# magic.net
KiCad netlist of a schematic drawn in EAGLE
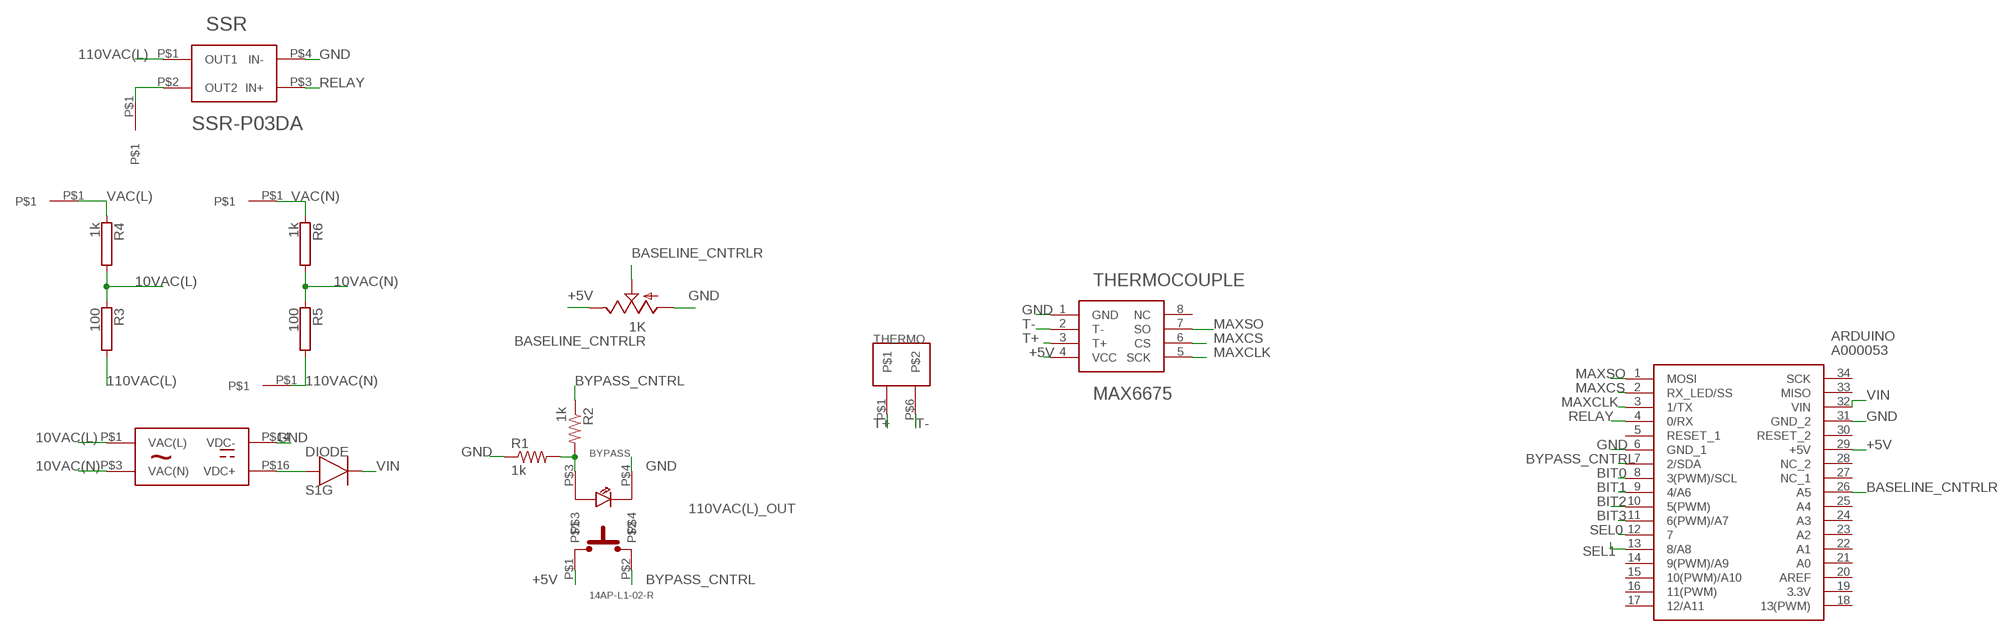
[diagram p0: schematic, sheet 1]
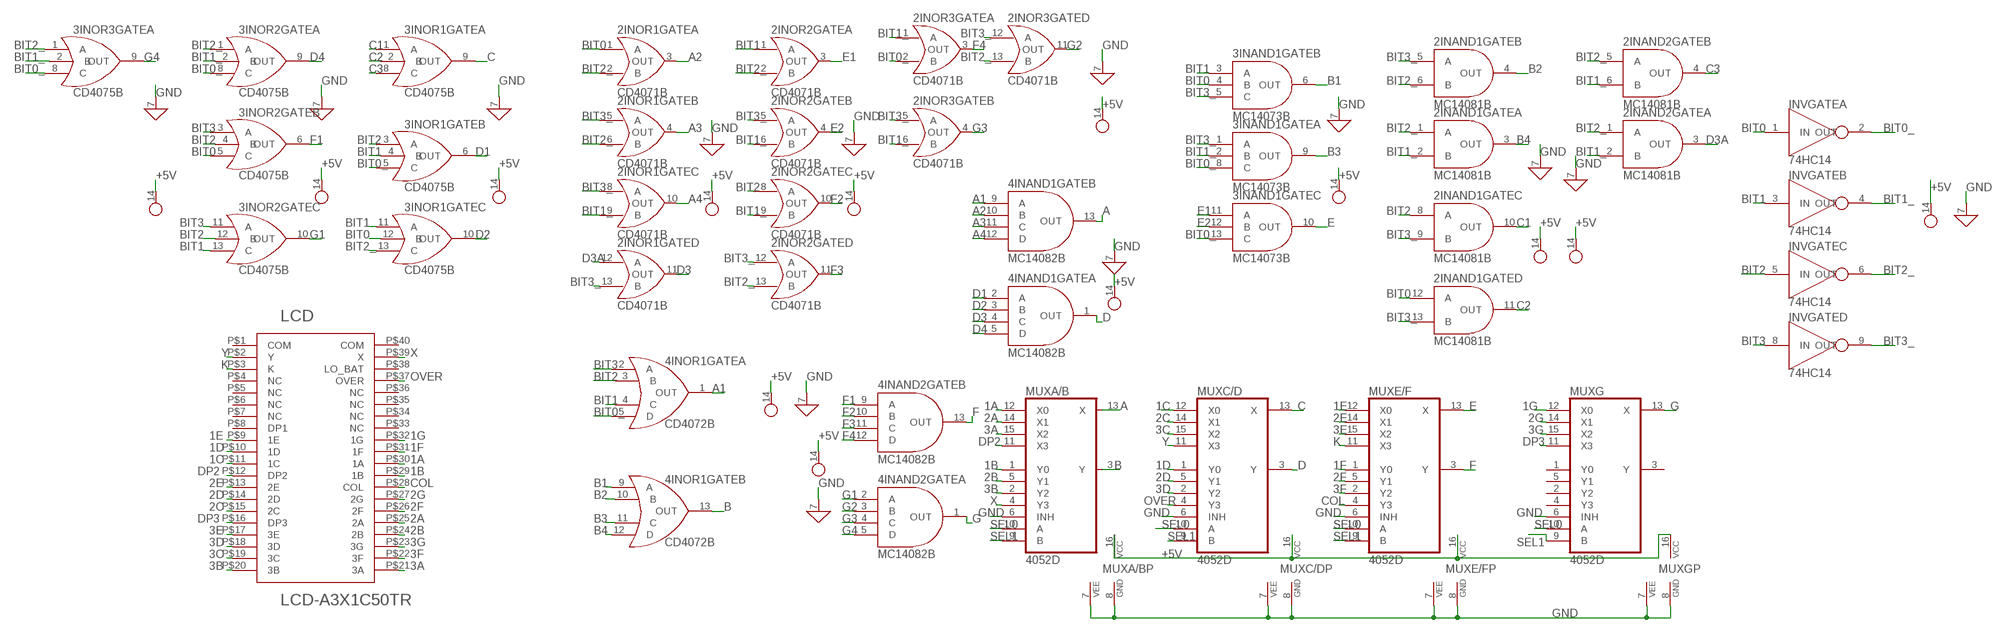
[diagram p1: schematic, sheet 2]

(export (version "E")
  (design (tool "Eeschema 10.0.6"))
  (components
    (comp (ref "110VAC(L)_OUT")
      (value "6-GAUGE")
      (footprint "eagle-import:6-GAUGE")
      (libsource (lib "eagle-import") (part "6-GAUGE"))
    )
    (comp (ref "110VAC(N)_OUT")
      (value "6-GAUGE")
      (footprint "eagle-import:6-GAUGE")
      (libsource (lib "eagle-import") (part "6-GAUGE"))
    )
    (comp (ref "AC(L)_IN")
      (value "6-GAUGE")
      (footprint "eagle-import:6-GAUGE")
      (libsource (lib "eagle-import") (part "6-GAUGE"))
    )
    (comp (ref "AC(N)_IN")
      (value "6-GAUGE")
      (footprint "eagle-import:6-GAUGE")
      (libsource (lib "eagle-import") (part "6-GAUGE"))
    )
    (comp (ref "ARDUINO")
      (value "A000053")
      (footprint "eagle-import:HDRV34W70P1570X254_2X17_4900X1")
      (fields (field (name "MOUSER_PART_NUMBER") "782-A000053") (field (name "RS_PART_NUMBER") "7717667"))
      (libsource (lib "eagle-import") (part "A000053"))
    )
    (comp (ref "BASELINE_CNTRLR")
      (value "1K")
      (footprint "eagle-import:PT-10")
      (libsource (lib "eagle-import") (part "TRIM_US-PT10"))
    )
    (comp (ref "BYPASS")
      (value "14AP-L1-02-R")
      (footprint "eagle-import:14XX-LX-0X-X")
      (libsource (lib "eagle-import") (part "14AP-L1-02-R"))
    )
    (comp (ref "DIODE")
      (value "S1G")
      (footprint "eagle-import:S1G")
      (libsource (lib "eagle-import") (part "S1G"))
    )
    (comp (ref "R1")
      (value "1k")
      (footprint "eagle-import:M1206")
      (libsource (lib "eagle-import") (part "R-US_M1206"))
    )
    (comp (ref "R2")
      (value "1k")
      (footprint "eagle-import:M1206")
      (libsource (lib "eagle-import") (part "R-US_M1206"))
    )
    (comp (ref "R3")
      (value "100")
      (footprint "eagle-import:TO-247-2V")
      (libsource (lib "eagle-import") (part "RMG100-V"))
    )
    (comp (ref "R4")
      (value "1k")
      (footprint "eagle-import:TO-247-2V")
      (libsource (lib "eagle-import") (part "RMG100-V"))
    )
    (comp (ref "R5")
      (value "100")
      (footprint "eagle-import:TO-247-2V")
      (libsource (lib "eagle-import") (part "RMG100-V"))
    )
    (comp (ref "R6")
      (value "1k")
      (footprint "eagle-import:TO-247-2V")
      (libsource (lib "eagle-import") (part "RMG100-V"))
    )
    (comp (ref "SSR")
      (value "SSR-P03DA")
      (footprint "eagle-import:SSR-P03DA")
      (libsource (lib "eagle-import") (part "SSR-P03DA"))
    )
    (comp (ref "THERMO")
      (value "PC6-16/2-G1-10,16")
      (footprint "eagle-import:PC6-16_2-G1-10,16")
      (libsource (lib "eagle-import") (part "PC6-16/2-G1-10,16"))
    )
    (comp (ref "THERMOCOUPLE")
      (value "MAX6675")
      (footprint "eagle-import:MAX6675")
      (libsource (lib "eagle-import") (part "MAX6675"))
    )
    (comp (ref "TRANSFORMER")
      (value "RAC04-09SC")
      (footprint "eagle-import:RAC04-09SC")
      (libsource (lib "eagle-import") (part "RAC04-09SC"))
    )
    (comp (ref "2INAND1")
      (value "MC14081B")
      (footprint "eagle-import:MC140XXBG")
      (libsource (lib "eagle-import") (part "MC14081B"))
    )
    (comp (ref "2INAND2")
      (value "MC14081B")
      (footprint "eagle-import:MC140XXBG")
      (libsource (lib "eagle-import") (part "MC14081B"))
    )
    (comp (ref "2INOR1")
      (value "CD4071B")
      (footprint "eagle-import:CD407XB")
      (libsource (lib "eagle-import") (part "CD4071B"))
    )
    (comp (ref "2INOR2")
      (value "CD4071B")
      (footprint "eagle-import:CD407XB")
      (libsource (lib "eagle-import") (part "CD4071B"))
    )
    (comp (ref "2INOR3")
      (value "CD4071B")
      (footprint "eagle-import:CD407XB")
      (libsource (lib "eagle-import") (part "CD4071B"))
    )
    (comp (ref "3INAND1")
      (value "MC14073B")
      (footprint "eagle-import:MC140XXBG")
      (libsource (lib "eagle-import") (part "MC14073B"))
    )
    (comp (ref "3INOR1")
      (value "CD4075B")
      (footprint "eagle-import:CD407XB")
      (libsource (lib "eagle-import") (part "CD4075B"))
    )
    (comp (ref "3INOR2")
      (value "CD4075B")
      (footprint "eagle-import:CD407XB")
      (libsource (lib "eagle-import") (part "CD4075B"))
    )
    (comp (ref "3INOR3")
      (value "CD4075B")
      (footprint "eagle-import:CD407XB")
      (libsource (lib "eagle-import") (part "CD4075B"))
    )
    (comp (ref "4INAND1")
      (value "MC14082B")
      (footprint "eagle-import:MC140XXBG")
      (libsource (lib "eagle-import") (part "MC14082B"))
    )
    (comp (ref "4INAND2")
      (value "MC14082B")
      (footprint "eagle-import:MC140XXBG")
      (libsource (lib "eagle-import") (part "MC14082B"))
    )
    (comp (ref "4INOR1")
      (value "CD4072B")
      (footprint "eagle-import:CD407XB")
      (libsource (lib "eagle-import") (part "CD4072B"))
    )
    (comp (ref "INV")
      (value "74HC14")
      (footprint "eagle-import:74HC14")
      (libsource (lib "eagle-import") (part "74HC14"))
    )
    (comp (ref "LCD")
      (value "LCD-A3X1C50TR")
      (footprint "eagle-import:LCD-A3X1C50TR")
      (libsource (lib "eagle-import") (part "LCD-A3X1C50TR"))
    )
    (comp (ref "MUXA/B")
      (value "4052D")
      (footprint "eagle-import:SO16")
      (libsource (lib "eagle-import") (part "4052D"))
    )
    (comp (ref "MUXC/D")
      (value "4052D")
      (footprint "eagle-import:SO16")
      (libsource (lib "eagle-import") (part "4052D"))
    )
    (comp (ref "MUXE/F")
      (value "4052D")
      (footprint "eagle-import:SO16")
      (libsource (lib "eagle-import") (part "4052D"))
    )
    (comp (ref "MUXG")
      (value "4052D")
      (footprint "eagle-import:SO16")
      (libsource (lib "eagle-import") (part "4052D"))
    )
  )
  (nets
    (net (code "1") (name "+5V") (class "Default")
      (node (ref "2INAND1") (pin "14") (pinfunction "1_14") (pintype "bidirectional"))
      (node (ref "2INAND2") (pin "14") (pinfunction "1_14") (pintype "bidirectional"))
      (node (ref "2INOR1") (pin "14") (pinfunction "1_14") (pintype "bidirectional"))
      (node (ref "2INOR2") (pin "14") (pinfunction "1_14") (pintype "bidirectional"))
      (node (ref "2INOR3") (pin "14") (pinfunction "1_14") (pintype "bidirectional"))
      (node (ref "3INAND1") (pin "14") (pinfunction "1_14") (pintype "bidirectional"))
      (node (ref "3INOR1") (pin "14") (pinfunction "1_14") (pintype "bidirectional"))
      (node (ref "3INOR2") (pin "14") (pinfunction "1_14") (pintype "bidirectional"))
      (node (ref "3INOR3") (pin "14") (pinfunction "1_14") (pintype "bidirectional"))
      (node (ref "4INAND1") (pin "14") (pinfunction "1_14") (pintype "bidirectional"))
      (node (ref "4INAND2") (pin "14") (pinfunction "1_14") (pintype "bidirectional"))
      (node (ref "4INOR1") (pin "14") (pinfunction "1_14") (pintype "bidirectional"))
      (node (ref "ARDUINO") (pin "29") (pinfunction "+5V_29") (pintype "bidirectional"))
      (node (ref "BASELINE_CNTRLR") (pin "E") (pinfunction "E_E") (pintype "passive"))
      (node (ref "BYPASS") (pin "P$1") (pinfunction "P$1_P$1") (pintype "bidirectional"))
      (node (ref "INV") (pin "14") (pinfunction "1_14") (pintype "bidirectional"))
      (node (ref "MUXA/B") (pin "16") (pinfunction "VCC_16") (pintype "power_in"))
      (node (ref "MUXC/D") (pin "16") (pinfunction "VCC_16") (pintype "power_in"))
      (node (ref "MUXE/F") (pin "16") (pinfunction "VCC_16") (pintype "power_in"))
      (node (ref "MUXG") (pin "16") (pinfunction "VCC_16") (pintype "power_in"))
      (node (ref "THERMOCOUPLE") (pin "4") (pinfunction "VCC_4") (pintype "bidirectional"))
    )
    (net (code "2") (name "1A") (class "Default")
      (node (ref "LCD") (pin "P$30") (pinfunction "1A_P$30") (pintype "bidirectional"))
      (node (ref "MUXA/B") (pin "12") (pinfunction "X0_12") (pintype "bidirectional"))
    )
    (net (code "3") (name "1B") (class "Default")
      (node (ref "LCD") (pin "P$29") (pinfunction "1B_P$29") (pintype "bidirectional"))
      (node (ref "MUXA/B") (pin "1") (pinfunction "Y0_1") (pintype "bidirectional"))
    )
    (net (code "4") (name "1C") (class "Default")
      (node (ref "LCD") (pin "P$11") (pinfunction "1C_P$11") (pintype "bidirectional"))
      (node (ref "MUXC/D") (pin "12") (pinfunction "X0_12") (pintype "bidirectional"))
    )
    (net (code "5") (name "1D") (class "Default")
      (node (ref "LCD") (pin "P$10") (pinfunction "1D_P$10") (pintype "bidirectional"))
      (node (ref "MUXC/D") (pin "1") (pinfunction "Y0_1") (pintype "bidirectional"))
    )
    (net (code "6") (name "1E") (class "Default")
      (node (ref "LCD") (pin "P$9") (pinfunction "1E_P$9") (pintype "bidirectional"))
      (node (ref "MUXE/F") (pin "12") (pinfunction "X0_12") (pintype "bidirectional"))
    )
    (net (code "7") (name "1F") (class "Default")
      (node (ref "LCD") (pin "P$31") (pinfunction "1F_P$31") (pintype "bidirectional"))
      (node (ref "MUXE/F") (pin "1") (pinfunction "Y0_1") (pintype "bidirectional"))
    )
    (net (code "8") (name "1G") (class "Default")
      (node (ref "LCD") (pin "P$32") (pinfunction "1G_P$32") (pintype "bidirectional"))
      (node (ref "MUXG") (pin "12") (pinfunction "X0_12") (pintype "bidirectional"))
    )
    (net (code "9") (name "2A") (class "Default")
      (node (ref "LCD") (pin "P$25") (pinfunction "2A_P$25") (pintype "bidirectional"))
      (node (ref "MUXA/B") (pin "14") (pinfunction "X1_14") (pintype "bidirectional"))
    )
    (net (code "10") (name "2B") (class "Default")
      (node (ref "LCD") (pin "P$24") (pinfunction "2B_P$24") (pintype "bidirectional"))
      (node (ref "MUXA/B") (pin "5") (pinfunction "Y1_5") (pintype "bidirectional"))
    )
    (net (code "11") (name "2C") (class "Default")
      (node (ref "LCD") (pin "P$15") (pinfunction "2C_P$15") (pintype "bidirectional"))
      (node (ref "MUXC/D") (pin "14") (pinfunction "X1_14") (pintype "bidirectional"))
    )
    (net (code "12") (name "2D") (class "Default")
      (node (ref "LCD") (pin "P$14") (pinfunction "2D_P$14") (pintype "bidirectional"))
      (node (ref "MUXC/D") (pin "5") (pinfunction "Y1_5") (pintype "bidirectional"))
    )
    (net (code "13") (name "2E") (class "Default")
      (node (ref "LCD") (pin "P$13") (pinfunction "2E_P$13") (pintype "bidirectional"))
      (node (ref "MUXE/F") (pin "14") (pinfunction "X1_14") (pintype "bidirectional"))
    )
    (net (code "14") (name "2F") (class "Default")
      (node (ref "LCD") (pin "P$26") (pinfunction "2F_P$26") (pintype "bidirectional"))
      (node (ref "MUXE/F") (pin "5") (pinfunction "Y1_5") (pintype "bidirectional"))
    )
    (net (code "15") (name "2G") (class "Default")
      (node (ref "LCD") (pin "P$27") (pinfunction "2G_P$27") (pintype "bidirectional"))
      (node (ref "MUXG") (pin "14") (pinfunction "X1_14") (pintype "bidirectional"))
    )
    (net (code "16") (name "3A") (class "Default")
      (node (ref "LCD") (pin "P$21") (pinfunction "3A_P$21") (pintype "bidirectional"))
      (node (ref "MUXA/B") (pin "15") (pinfunction "X2_15") (pintype "bidirectional"))
    )
    (net (code "17") (name "3B") (class "Default")
      (node (ref "LCD") (pin "P$20") (pinfunction "3B_P$20") (pintype "bidirectional"))
      (node (ref "MUXA/B") (pin "2") (pinfunction "Y2_2") (pintype "bidirectional"))
    )
    (net (code "18") (name "3C") (class "Default")
      (node (ref "LCD") (pin "P$19") (pinfunction "3C_P$19") (pintype "bidirectional"))
      (node (ref "MUXC/D") (pin "15") (pinfunction "X2_15") (pintype "bidirectional"))
    )
    (net (code "19") (name "3D") (class "Default")
      (node (ref "LCD") (pin "P$18") (pinfunction "3D_P$18") (pintype "bidirectional"))
      (node (ref "MUXC/D") (pin "2") (pinfunction "Y2_2") (pintype "bidirectional"))
    )
    (net (code "20") (name "3E") (class "Default")
      (node (ref "LCD") (pin "P$17") (pinfunction "3E_P$17") (pintype "bidirectional"))
      (node (ref "MUXE/F") (pin "15") (pinfunction "X2_15") (pintype "bidirectional"))
    )
    (net (code "21") (name "3F") (class "Default")
      (node (ref "LCD") (pin "P$22") (pinfunction "3F_P$22") (pintype "bidirectional"))
      (node (ref "MUXE/F") (pin "2") (pinfunction "Y2_2") (pintype "bidirectional"))
    )
    (net (code "22") (name "3G") (class "Default")
      (node (ref "LCD") (pin "P$23") (pinfunction "3G_P$23") (pintype "bidirectional"))
      (node (ref "MUXG") (pin "15") (pinfunction "X2_15") (pintype "bidirectional"))
    )
    (net (code "23") (name "10VAC(L)") (class "Default")
      (node (ref "R3") (pin "1") (pinfunction "1_1") (pintype "passive"))
      (node (ref "R4") (pin "2") (pinfunction "2_2") (pintype "passive"))
      (node (ref "TRANSFORMER") (pin "P$1") (pinfunction "VAC(L)_P$1") (pintype "bidirectional"))
    )
    (net (code "24") (name "10VAC(N)") (class "Default")
      (node (ref "R5") (pin "1") (pinfunction "1_1") (pintype "passive"))
      (node (ref "R6") (pin "2") (pinfunction "2_2") (pintype "passive"))
      (node (ref "TRANSFORMER") (pin "P$3") (pinfunction "VAC(N)_P$3") (pintype "bidirectional"))
    )
    (net (code "25") (name "110VAC(L)") (class "Default")
      (node (ref "R3") (pin "2") (pinfunction "2_2") (pintype "passive"))
      (node (ref "SSR") (pin "P$1") (pinfunction "OUT1_P$1") (pintype "bidirectional"))
    )
    (net (code "26") (name "110VAC(L)_OUT") (class "Default")
      (node (ref "110VAC(L)_OUT") (pin "P$1") (pinfunction "P$1_P$1") (pintype "bidirectional"))
      (node (ref "SSR") (pin "P$2") (pinfunction "OUT2_P$2") (pintype "bidirectional"))
    )
    (net (code "27") (name "110VAC(N)") (class "Default")
      (node (ref "110VAC(N)_OUT") (pin "P$1") (pinfunction "P$1_P$1") (pintype "bidirectional"))
      (node (ref "R5") (pin "2") (pinfunction "2_2") (pintype "passive"))
    )
    (net (code "28") (name "A") (class "Default")
      (node (ref "4INAND1") (pin "13") (pinfunction "OUT_13") (pintype "bidirectional"))
      (node (ref "MUXA/B") (pin "13") (pinfunction "X_13") (pintype "bidirectional"))
    )
    (net (code "29") (name "A1") (class "Default")
      (node (ref "4INAND1") (pin "9") (pinfunction "A_9") (pintype "bidirectional"))
      (node (ref "4INOR1") (pin "1") (pinfunction "OUT_1") (pintype "bidirectional"))
    )
    (net (code "30") (name "A2") (class "Default")
      (node (ref "2INOR1") (pin "3") (pinfunction "OUT_3") (pintype "bidirectional"))
      (node (ref "4INAND1") (pin "10") (pinfunction "B_10") (pintype "bidirectional"))
    )
    (net (code "31") (name "A3") (class "Default")
      (node (ref "2INOR1") (pin "4") (pinfunction "OUT_4") (pintype "bidirectional"))
      (node (ref "4INAND1") (pin "11") (pinfunction "C_11") (pintype "bidirectional"))
    )
    (net (code "32") (name "A4") (class "Default")
      (node (ref "2INOR1") (pin "10") (pinfunction "OUT_10") (pintype "bidirectional"))
      (node (ref "4INAND1") (pin "12") (pinfunction "D_12") (pintype "bidirectional"))
    )
    (net (code "33") (name "B") (class "Default")
      (node (ref "4INOR1") (pin "13") (pinfunction "OUT_13") (pintype "bidirectional"))
      (node (ref "MUXA/B") (pin "3") (pinfunction "Y_3") (pintype "bidirectional"))
    )
    (net (code "34") (name "B1") (class "Default")
      (node (ref "3INAND1") (pin "6") (pinfunction "OUT_6") (pintype "bidirectional"))
      (node (ref "4INOR1") (pin "9") (pinfunction "A_9") (pintype "bidirectional"))
    )
    (net (code "35") (name "B2") (class "Default")
      (node (ref "2INAND1") (pin "4") (pinfunction "OUT_4") (pintype "bidirectional"))
      (node (ref "4INOR1") (pin "10") (pinfunction "B_10") (pintype "bidirectional"))
    )
    (net (code "36") (name "B3") (class "Default")
      (node (ref "3INAND1") (pin "9") (pinfunction "OUT_9") (pintype "bidirectional"))
      (node (ref "4INOR1") (pin "11") (pinfunction "C_11") (pintype "bidirectional"))
    )
    (net (code "37") (name "B4") (class "Default")
      (node (ref "2INAND1") (pin "3") (pinfunction "OUT_3") (pintype "bidirectional"))
      (node (ref "4INOR1") (pin "12") (pinfunction "D_12") (pintype "bidirectional"))
    )
    (net (code "38") (name "BASELINE_CNTRLR") (class "Default")
      (node (ref "ARDUINO") (pin "26") (pinfunction "A5_26") (pintype "bidirectional"))
      (node (ref "BASELINE_CNTRLR") (pin "S") (pinfunction "S_S") (pintype "passive"))
    )
    (net (code "39") (name "BIT0") (class "Default")
      (node (ref "2INAND1") (pin "12") (pinfunction "A_12") (pintype "bidirectional"))
      (node (ref "2INOR1") (pin "1") (pinfunction "A_1") (pintype "bidirectional"))
      (node (ref "3INAND1") (pin "4") (pinfunction "B_4") (pintype "bidirectional"))
      (node (ref "3INOR1") (pin "12") (pinfunction "B_12") (pintype "bidirectional"))
      (node (ref "3INOR2") (pin "5") (pinfunction "C_5") (pintype "bidirectional"))
      (node (ref "ARDUINO") (pin "8") (pinfunction "3(PWM)/SCL_8") (pintype "bidirectional"))
      (node (ref "INV") (pin "1") (pinfunction "IN_1") (pintype "bidirectional"))
    )
    (net (code "40") (name "BIT0_") (class "Default")
      (node (ref "2INOR3") (pin "2") (pinfunction "B_2") (pintype "bidirectional"))
      (node (ref "3INAND1") (pin "13") (pinfunction "C_13") (pintype "bidirectional"))
      (node (ref "3INAND1") (pin "8") (pinfunction "C_8") (pintype "bidirectional"))
      (node (ref "3INOR1") (pin "5") (pinfunction "C_5") (pintype "bidirectional"))
      (node (ref "3INOR2") (pin "8") (pinfunction "C_8") (pintype "bidirectional"))
      (node (ref "3INOR3") (pin "8") (pinfunction "C_8") (pintype "bidirectional"))
      (node (ref "4INOR1") (pin "5") (pinfunction "D_5") (pintype "bidirectional"))
      (node (ref "INV") (pin "2") (pinfunction "OUT_2") (pintype "bidirectional"))
    )
    (net (code "41") (name "BIT1") (class "Default")
      (node (ref "2INOR2") (pin "1") (pinfunction "A_1") (pintype "bidirectional"))
      (node (ref "3INAND1") (pin "3") (pinfunction "A_3") (pintype "bidirectional"))
      (node (ref "3INOR1") (pin "11") (pinfunction "A_11") (pintype "bidirectional"))
      (node (ref "3INOR1") (pin "4") (pinfunction "B_4") (pintype "bidirectional"))
      (node (ref "3INOR2") (pin "13") (pinfunction "C_13") (pintype "bidirectional"))
      (node (ref "4INOR1") (pin "4") (pinfunction "C_4") (pintype "bidirectional"))
      (node (ref "ARDUINO") (pin "9") (pinfunction "4/A6_9") (pintype "bidirectional"))
      (node (ref "INV") (pin "3") (pinfunction "IN_3") (pintype "bidirectional"))
    )
    (net (code "42") (name "BIT1_") (class "Default")
      (node (ref "2INAND1") (pin "2") (pinfunction "B_2") (pintype "bidirectional"))
      (node (ref "2INAND2") (pin "2") (pinfunction "B_2") (pintype "bidirectional"))
      (node (ref "2INAND2") (pin "6") (pinfunction "B_6") (pintype "bidirectional"))
      (node (ref "2INOR1") (pin "9") (pinfunction "B_9") (pintype "bidirectional"))
      (node (ref "2INOR2") (pin "6") (pinfunction "B_6") (pintype "bidirectional"))
      (node (ref "2INOR2") (pin "9") (pinfunction "B_9") (pintype "bidirectional"))
      (node (ref "2INOR3") (pin "1") (pinfunction "A_1") (pintype "bidirectional"))
      (node (ref "2INOR3") (pin "6") (pinfunction "B_6") (pintype "bidirectional"))
      (node (ref "3INAND1") (pin "2") (pinfunction "B_2") (pintype "bidirectional"))
      (node (ref "3INOR2") (pin "2") (pinfunction "B_2") (pintype "bidirectional"))
      (node (ref "3INOR3") (pin "2") (pinfunction "B_2") (pintype "bidirectional"))
      (node (ref "INV") (pin "4") (pinfunction "OUT_4") (pintype "bidirectional"))
    )
    (net (code "43") (name "BIT2") (class "Default")
      (node (ref "2INAND1") (pin "8") (pinfunction "A_8") (pintype "bidirectional"))
      (node (ref "2INOR2") (pin "8") (pinfunction "A_8") (pintype "bidirectional"))
      (node (ref "3INOR1") (pin "3") (pinfunction "A_3") (pintype "bidirectional"))
      (node (ref "3INOR2") (pin "12") (pinfunction "B_12") (pintype "bidirectional"))
      (node (ref "3INOR2") (pin "4") (pinfunction "B_4") (pintype "bidirectional"))
      (node (ref "4INOR1") (pin "3") (pinfunction "B_3") (pintype "bidirectional"))
      (node (ref "ARDUINO") (pin "10") (pinfunction "5(PWM)_10") (pintype "bidirectional"))
      (node (ref "INV") (pin "5") (pinfunction "IN_5") (pintype "bidirectional"))
    )
    (net (code "44") (name "BIT2_") (class "Default")
      (node (ref "2INAND1") (pin "1") (pinfunction "A_1") (pintype "bidirectional"))
      (node (ref "2INAND1") (pin "6") (pinfunction "B_6") (pintype "bidirectional"))
      (node (ref "2INAND2") (pin "1") (pinfunction "A_1") (pintype "bidirectional"))
      (node (ref "2INAND2") (pin "5") (pinfunction "A_5") (pintype "bidirectional"))
      (node (ref "2INOR1") (pin "2") (pinfunction "B_2") (pintype "bidirectional"))
      (node (ref "2INOR1") (pin "6") (pinfunction "B_6") (pintype "bidirectional"))
      (node (ref "2INOR2") (pin "13") (pinfunction "B_13") (pintype "bidirectional"))
      (node (ref "2INOR2") (pin "2") (pinfunction "B_2") (pintype "bidirectional"))
      (node (ref "2INOR3") (pin "13") (pinfunction "B_13") (pintype "bidirectional"))
      (node (ref "3INOR1") (pin "13") (pinfunction "C_13") (pintype "bidirectional"))
      (node (ref "3INOR2") (pin "1") (pinfunction "A_1") (pintype "bidirectional"))
      (node (ref "3INOR3") (pin "1") (pinfunction "A_1") (pintype "bidirectional"))
      (node (ref "INV") (pin "6") (pinfunction "OUT_6") (pintype "bidirectional"))
    )
    (net (code "45") (name "BIT3") (class "Default")
      (node (ref "3INOR2") (pin "11") (pinfunction "A_11") (pintype "bidirectional"))
      (node (ref "3INOR2") (pin "3") (pinfunction "A_3") (pintype "bidirectional"))
      (node (ref "4INOR1") (pin "2") (pinfunction "A_2") (pintype "bidirectional"))
      (node (ref "ARDUINO") (pin "11") (pinfunction "6(PWM)/A7_11") (pintype "bidirectional"))
      (node (ref "INV") (pin "8") (pinfunction "IN_8") (pintype "bidirectional"))
    )
    (net (code "46") (name "BIT3_") (class "Default")
      (node (ref "2INAND1") (pin "13") (pinfunction "B_13") (pintype "bidirectional"))
      (node (ref "2INAND1") (pin "5") (pinfunction "A_5") (pintype "bidirectional"))
      (node (ref "2INAND1") (pin "9") (pinfunction "B_9") (pintype "bidirectional"))
      (node (ref "2INOR1") (pin "13") (pinfunction "B_13") (pintype "bidirectional"))
      (node (ref "2INOR1") (pin "5") (pinfunction "A_5") (pintype "bidirectional"))
      (node (ref "2INOR1") (pin "8") (pinfunction "A_8") (pintype "bidirectional"))
      (node (ref "2INOR2") (pin "12") (pinfunction "A_12") (pintype "bidirectional"))
      (node (ref "2INOR2") (pin "5") (pinfunction "A_5") (pintype "bidirectional"))
      (node (ref "2INOR3") (pin "12") (pinfunction "A_12") (pintype "bidirectional"))
      (node (ref "2INOR3") (pin "5") (pinfunction "A_5") (pintype "bidirectional"))
      (node (ref "3INAND1") (pin "1") (pinfunction "A_1") (pintype "bidirectional"))
      (node (ref "3INAND1") (pin "5") (pinfunction "C_5") (pintype "bidirectional"))
      (node (ref "INV") (pin "9") (pinfunction "OUT_9") (pintype "bidirectional"))
    )
    (net (code "47") (name "BYPASS_CNTRL") (class "Default")
      (node (ref "ARDUINO") (pin "7") (pinfunction "2/SDA_7") (pintype "bidirectional"))
      (node (ref "BYPASS") (pin "P$2") (pinfunction "P$2_P$2") (pintype "bidirectional"))
      (node (ref "R2") (pin "1") (pinfunction "1_1") (pintype "passive"))
    )
    (net (code "48") (name "C") (class "Default")
      (node (ref "3INOR1") (pin "9") (pinfunction "OUT_9") (pintype "bidirectional"))
      (node (ref "MUXC/D") (pin "13") (pinfunction "X_13") (pintype "bidirectional"))
    )
    (net (code "49") (name "C1") (class "Default")
      (node (ref "2INAND1") (pin "10") (pinfunction "OUT_10") (pintype "bidirectional"))
      (node (ref "3INOR1") (pin "1") (pinfunction "A_1") (pintype "bidirectional"))
    )
    (net (code "50") (name "C2") (class "Default")
      (node (ref "2INAND1") (pin "11") (pinfunction "OUT_11") (pintype "bidirectional"))
      (node (ref "3INOR1") (pin "2") (pinfunction "B_2") (pintype "bidirectional"))
    )
    (net (code "51") (name "C3") (class "Default")
      (node (ref "2INAND2") (pin "4") (pinfunction "OUT_4") (pintype "bidirectional"))
      (node (ref "3INOR1") (pin "8") (pinfunction "C_8") (pintype "bidirectional"))
    )
    (net (code "52") (name "COL") (class "Default")
      (node (ref "LCD") (pin "P$28") (pinfunction "COL_P$28") (pintype "bidirectional"))
      (node (ref "MUXE/F") (pin "4") (pinfunction "Y3_4") (pintype "bidirectional"))
    )
    (net (code "53") (name "D") (class "Default")
      (node (ref "4INAND1") (pin "1") (pinfunction "OUT_1") (pintype "bidirectional"))
      (node (ref "MUXC/D") (pin "3") (pinfunction "Y_3") (pintype "bidirectional"))
    )
    (net (code "54") (name "D1") (class "Default")
      (node (ref "3INOR1") (pin "6") (pinfunction "OUT_6") (pintype "bidirectional"))
      (node (ref "4INAND1") (pin "2") (pinfunction "A_2") (pintype "bidirectional"))
    )
    (net (code "55") (name "D2") (class "Default")
      (node (ref "3INOR1") (pin "10") (pinfunction "OUT_10") (pintype "bidirectional"))
      (node (ref "4INAND1") (pin "3") (pinfunction "B_3") (pintype "bidirectional"))
    )
    (net (code "56") (name "D3") (class "Default")
      (node (ref "2INOR1") (pin "11") (pinfunction "OUT_11") (pintype "bidirectional"))
      (node (ref "4INAND1") (pin "4") (pinfunction "C_4") (pintype "bidirectional"))
    )
    (net (code "57") (name "D3A") (class "Default")
      (node (ref "2INAND2") (pin "3") (pinfunction "OUT_3") (pintype "bidirectional"))
      (node (ref "2INOR1") (pin "12") (pinfunction "A_12") (pintype "bidirectional"))
    )
    (net (code "58") (name "D4") (class "Default")
      (node (ref "3INOR2") (pin "9") (pinfunction "OUT_9") (pintype "bidirectional"))
      (node (ref "4INAND1") (pin "5") (pinfunction "D_5") (pintype "bidirectional"))
    )
    (net (code "59") (name "DP2") (class "Default")
      (node (ref "LCD") (pin "P$12") (pinfunction "DP2_P$12") (pintype "bidirectional"))
      (node (ref "MUXA/B") (pin "11") (pinfunction "X3_11") (pintype "bidirectional"))
    )
    (net (code "60") (name "DP3") (class "Default")
      (node (ref "LCD") (pin "P$16") (pinfunction "DP3_P$16") (pintype "bidirectional"))
      (node (ref "MUXG") (pin "11") (pinfunction "X3_11") (pintype "bidirectional"))
    )
    (net (code "61") (name "E") (class "Default")
      (node (ref "3INAND1") (pin "10") (pinfunction "OUT_10") (pintype "bidirectional"))
      (node (ref "MUXE/F") (pin "13") (pinfunction "X_13") (pintype "bidirectional"))
    )
    (net (code "62") (name "E1") (class "Default")
      (node (ref "2INOR2") (pin "3") (pinfunction "OUT_3") (pintype "bidirectional"))
      (node (ref "3INAND1") (pin "11") (pinfunction "A_11") (pintype "bidirectional"))
    )
    (net (code "63") (name "E2") (class "Default")
      (node (ref "2INOR2") (pin "4") (pinfunction "OUT_4") (pintype "bidirectional"))
      (node (ref "3INAND1") (pin "12") (pinfunction "B_12") (pintype "bidirectional"))
    )
    (net (code "64") (name "F") (class "Default")
      (node (ref "4INAND2") (pin "13") (pinfunction "OUT_13") (pintype "bidirectional"))
      (node (ref "MUXE/F") (pin "3") (pinfunction "Y_3") (pintype "bidirectional"))
    )
    (net (code "65") (name "F1") (class "Default")
      (node (ref "3INOR2") (pin "6") (pinfunction "OUT_6") (pintype "bidirectional"))
      (node (ref "4INAND2") (pin "9") (pinfunction "A_9") (pintype "bidirectional"))
    )
    (net (code "66") (name "F2") (class "Default")
      (node (ref "2INOR2") (pin "10") (pinfunction "OUT_10") (pintype "bidirectional"))
      (node (ref "4INAND2") (pin "10") (pinfunction "B_10") (pintype "bidirectional"))
    )
    (net (code "67") (name "F3") (class "Default")
      (node (ref "2INOR2") (pin "11") (pinfunction "OUT_11") (pintype "bidirectional"))
      (node (ref "4INAND2") (pin "11") (pinfunction "C_11") (pintype "bidirectional"))
    )
    (net (code "68") (name "F4") (class "Default")
      (node (ref "2INOR3") (pin "3") (pinfunction "OUT_3") (pintype "bidirectional"))
      (node (ref "4INAND2") (pin "12") (pinfunction "D_12") (pintype "bidirectional"))
    )
    (net (code "69") (name "G") (class "Default")
      (node (ref "4INAND2") (pin "1") (pinfunction "OUT_1") (pintype "bidirectional"))
      (node (ref "MUXG") (pin "13") (pinfunction "X_13") (pintype "bidirectional"))
    )
    (net (code "70") (name "G1") (class "Default")
      (node (ref "3INOR2") (pin "10") (pinfunction "OUT_10") (pintype "bidirectional"))
      (node (ref "4INAND2") (pin "2") (pinfunction "A_2") (pintype "bidirectional"))
    )
    (net (code "71") (name "G2") (class "Default")
      (node (ref "2INOR3") (pin "11") (pinfunction "OUT_11") (pintype "bidirectional"))
      (node (ref "4INAND2") (pin "3") (pinfunction "B_3") (pintype "bidirectional"))
    )
    (net (code "72") (name "G3") (class "Default")
      (node (ref "2INOR3") (pin "4") (pinfunction "OUT_4") (pintype "bidirectional"))
      (node (ref "4INAND2") (pin "4") (pinfunction "C_4") (pintype "bidirectional"))
    )
    (net (code "73") (name "G4") (class "Default")
      (node (ref "3INOR3") (pin "9") (pinfunction "OUT_9") (pintype "bidirectional"))
      (node (ref "4INAND2") (pin "5") (pinfunction "D_5") (pintype "bidirectional"))
    )
    (net (code "74") (name "GND") (class "Default")
      (node (ref "2INAND1") (pin "7") (pinfunction "1_7") (pintype "bidirectional"))
      (node (ref "2INAND2") (pin "7") (pinfunction "1_7") (pintype "bidirectional"))
      (node (ref "2INOR1") (pin "7") (pinfunction "1_7") (pintype "bidirectional"))
      (node (ref "2INOR2") (pin "7") (pinfunction "1_7") (pintype "bidirectional"))
      (node (ref "2INOR3") (pin "7") (pinfunction "1_7") (pintype "bidirectional"))
      (node (ref "3INAND1") (pin "7") (pinfunction "1_7") (pintype "bidirectional"))
      (node (ref "3INOR1") (pin "7") (pinfunction "1_7") (pintype "bidirectional"))
      (node (ref "3INOR2") (pin "7") (pinfunction "1_7") (pintype "bidirectional"))
      (node (ref "3INOR3") (pin "7") (pinfunction "1_7") (pintype "bidirectional"))
      (node (ref "4INAND1") (pin "7") (pinfunction "1_7") (pintype "bidirectional"))
      (node (ref "4INAND2") (pin "7") (pinfunction "1_7") (pintype "bidirectional"))
      (node (ref "4INOR1") (pin "7") (pinfunction "1_7") (pintype "bidirectional"))
      (node (ref "ARDUINO") (pin "31") (pinfunction "GND_2_31") (pintype "bidirectional"))
      (node (ref "ARDUINO") (pin "6") (pinfunction "GND_1_6") (pintype "power_in"))
      (node (ref "BASELINE_CNTRLR") (pin "A") (pinfunction "A_A") (pintype "passive"))
      (node (ref "BYPASS") (pin "P$4") (pinfunction "P$4_P$4") (pintype "bidirectional"))
      (node (ref "INV") (pin "7") (pinfunction "1_7") (pintype "bidirectional"))
      (node (ref "MUXA/B") (pin "6") (pinfunction "INH_6") (pintype "input"))
      (node (ref "MUXA/B") (pin "7") (pinfunction "VEE_7") (pintype "power_in"))
      (node (ref "MUXA/B") (pin "8") (pinfunction "GND_8") (pintype "power_in"))
      (node (ref "MUXC/D") (pin "6") (pinfunction "INH_6") (pintype "input"))
      (node (ref "MUXC/D") (pin "7") (pinfunction "VEE_7") (pintype "power_in"))
      (node (ref "MUXC/D") (pin "8") (pinfunction "GND_8") (pintype "power_in"))
      (node (ref "MUXE/F") (pin "6") (pinfunction "INH_6") (pintype "input"))
      (node (ref "MUXE/F") (pin "7") (pinfunction "VEE_7") (pintype "power_in"))
      (node (ref "MUXE/F") (pin "8") (pinfunction "GND_8") (pintype "power_in"))
      (node (ref "MUXG") (pin "6") (pinfunction "INH_6") (pintype "input"))
      (node (ref "MUXG") (pin "7") (pinfunction "VEE_7") (pintype "power_in"))
      (node (ref "MUXG") (pin "8") (pinfunction "GND_8") (pintype "power_in"))
      (node (ref "R1") (pin "1") (pinfunction "1_1") (pintype "passive"))
      (node (ref "SSR") (pin "P$4") (pinfunction "IN-_P$4") (pintype "bidirectional"))
      (node (ref "THERMOCOUPLE") (pin "1") (pinfunction "GND_1") (pintype "bidirectional"))
      (node (ref "TRANSFORMER") (pin "P$14") (pinfunction "VDC-_P$14") (pintype "bidirectional"))
    )
    (net (code "75") (name "K") (class "Default")
      (node (ref "LCD") (pin "P$3") (pinfunction "K_P$3") (pintype "bidirectional"))
      (node (ref "MUXE/F") (pin "11") (pinfunction "X3_11") (pintype "bidirectional"))
    )
    (net (code "76") (name "MAXCLK") (class "Default")
      (node (ref "ARDUINO") (pin "3") (pinfunction "1/TX_3") (pintype "bidirectional"))
      (node (ref "THERMOCOUPLE") (pin "5") (pinfunction "SCK_5") (pintype "bidirectional"))
    )
    (net (code "77") (name "MAXCS") (class "Default")
      (node (ref "ARDUINO") (pin "2") (pinfunction "RX_LED/SS_2") (pintype "bidirectional"))
      (node (ref "THERMOCOUPLE") (pin "6") (pinfunction "CS_6") (pintype "bidirectional"))
    )
    (net (code "78") (name "MAXSO") (class "Default")
      (node (ref "ARDUINO") (pin "1") (pinfunction "MOSI_1") (pintype "bidirectional"))
      (node (ref "THERMOCOUPLE") (pin "7") (pinfunction "SO_7") (pintype "bidirectional"))
    )
    (net (code "79") (name "Net-(BYPASS-PadP$3)") (class "Default")
      (node (ref "BYPASS") (pin "P$3") (pinfunction "P$3_P$3") (pintype "bidirectional"))
      (node (ref "R1") (pin "2") (pinfunction "2_2") (pintype "passive"))
      (node (ref "R2") (pin "2") (pinfunction "2_2") (pintype "passive"))
    )
    (net (code "80") (name "Net-(DIODE-P$1)") (class "Default")
      (node (ref "DIODE") (pin "2") (pinfunction "P$1_2") (pintype "bidirectional"))
      (node (ref "TRANSFORMER") (pin "P$16") (pinfunction "VDC+_P$16") (pintype "bidirectional"))
    )
    (net (code "81") (name "OVER") (class "Default")
      (node (ref "LCD") (pin "P$37") (pinfunction "OVER_P$37") (pintype "bidirectional"))
      (node (ref "MUXC/D") (pin "4") (pinfunction "Y3_4") (pintype "bidirectional"))
    )
    (net (code "82") (name "RELAY") (class "Default")
      (node (ref "ARDUINO") (pin "4") (pinfunction "0/RX_4") (pintype "bidirectional"))
      (node (ref "SSR") (pin "P$3") (pinfunction "IN+_P$3") (pintype "bidirectional"))
    )
    (net (code "83") (name "SEL0") (class "Default")
      (node (ref "ARDUINO") (pin "12") (pinfunction "7_12") (pintype "bidirectional"))
      (node (ref "MUXA/B") (pin "10") (pinfunction "A_10") (pintype "input"))
      (node (ref "MUXC/D") (pin "10") (pinfunction "A_10") (pintype "input"))
      (node (ref "MUXE/F") (pin "10") (pinfunction "A_10") (pintype "input"))
      (node (ref "MUXG") (pin "10") (pinfunction "A_10") (pintype "input"))
    )
    (net (code "84") (name "SEL1") (class "Default")
      (node (ref "ARDUINO") (pin "13") (pinfunction "8/A8_13") (pintype "bidirectional"))
      (node (ref "MUXA/B") (pin "9") (pinfunction "B_9") (pintype "input"))
      (node (ref "MUXC/D") (pin "9") (pinfunction "B_9") (pintype "input"))
      (node (ref "MUXE/F") (pin "9") (pinfunction "B_9") (pintype "input"))
      (node (ref "MUXG") (pin "9") (pinfunction "B_9") (pintype "input"))
    )
    (net (code "85") (name "T+") (class "Default")
      (node (ref "THERMO") (pin "P$1") (pinfunction "P$1_P$1") (pintype "bidirectional"))
      (node (ref "THERMOCOUPLE") (pin "3") (pinfunction "T+_3") (pintype "bidirectional"))
    )
    (net (code "86") (name "T-") (class "Default")
      (node (ref "THERMO") (pin "P$6") (pinfunction "P$2_P$6") (pintype "bidirectional"))
      (node (ref "THERMOCOUPLE") (pin "2") (pinfunction "T-_2") (pintype "bidirectional"))
    )
    (net (code "87") (name "VAC(L)") (class "Default")
      (node (ref "AC(L)_IN") (pin "P$1") (pinfunction "P$1_P$1") (pintype "bidirectional"))
      (node (ref "R4") (pin "1") (pinfunction "1_1") (pintype "passive"))
    )
    (net (code "88") (name "VAC(N)") (class "Default")
      (node (ref "AC(N)_IN") (pin "P$1") (pinfunction "P$1_P$1") (pintype "bidirectional"))
      (node (ref "R6") (pin "1") (pinfunction "1_1") (pintype "passive"))
    )
    (net (code "89") (name "VIN") (class "Default")
      (node (ref "ARDUINO") (pin "32") (pinfunction "VIN_32") (pintype "bidirectional"))
      (node (ref "DIODE") (pin "1") (pinfunction "P$2_1") (pintype "bidirectional"))
    )
    (net (code "90") (name "X") (class "Default")
      (node (ref "LCD") (pin "P$39") (pinfunction "X_P$39") (pintype "bidirectional"))
      (node (ref "MUXA/B") (pin "4") (pinfunction "Y3_4") (pintype "bidirectional"))
    )
    (net (code "91") (name "Y") (class "Default")
      (node (ref "LCD") (pin "P$2") (pinfunction "Y_P$2") (pintype "bidirectional"))
      (node (ref "MUXC/D") (pin "11") (pinfunction "X3_11") (pintype "bidirectional"))
    )
    (net (code "92") (name "unconnected-(ARDUINO-3.3V-Pad19)") (class "Default")
      (node (ref "ARDUINO") (pin "19") (pinfunction "3.3V_19") (pintype "bidirectional"))
    )
    (net (code "93") (name "unconnected-(ARDUINO-9(PWM){slash}A9-Pad14)") (class "Default")
      (node (ref "ARDUINO") (pin "14") (pinfunction "9(PWM)/A9_14") (pintype "bidirectional"))
    )
    (net (code "94") (name "unconnected-(ARDUINO-10(PWM){slash}A10-Pad15)") (class "Default")
      (node (ref "ARDUINO") (pin "15") (pinfunction "10(PWM)/A10_15") (pintype "bidirectional"))
    )
    (net (code "95") (name "unconnected-(ARDUINO-11(PWM)-Pad16)") (class "Default")
      (node (ref "ARDUINO") (pin "16") (pinfunction "11(PWM)_16") (pintype "bidirectional"))
    )
    (net (code "96") (name "unconnected-(ARDUINO-12{slash}A11-Pad17)") (class "Default")
      (node (ref "ARDUINO") (pin "17") (pinfunction "12/A11_17") (pintype "bidirectional"))
    )
    (net (code "97") (name "unconnected-(ARDUINO-13(PWM)-Pad18)") (class "Default")
      (node (ref "ARDUINO") (pin "18") (pinfunction "13(PWM)_18") (pintype "bidirectional"))
    )
    (net (code "98") (name "unconnected-(ARDUINO-A0-Pad21)") (class "Default")
      (node (ref "ARDUINO") (pin "21") (pinfunction "A0_21") (pintype "bidirectional"))
    )
    (net (code "99") (name "unconnected-(ARDUINO-A1-Pad22)") (class "Default")
      (node (ref "ARDUINO") (pin "22") (pinfunction "A1_22") (pintype "bidirectional"))
    )
    (net (code "100") (name "unconnected-(ARDUINO-A2-Pad23)") (class "Default")
      (node (ref "ARDUINO") (pin "23") (pinfunction "A2_23") (pintype "bidirectional"))
    )
    (net (code "101") (name "unconnected-(ARDUINO-A3-Pad24)") (class "Default")
      (node (ref "ARDUINO") (pin "24") (pinfunction "A3_24") (pintype "bidirectional"))
    )
    (net (code "102") (name "unconnected-(ARDUINO-A4-Pad25)") (class "Default")
      (node (ref "ARDUINO") (pin "25") (pinfunction "A4_25") (pintype "bidirectional"))
    )
    (net (code "103") (name "unconnected-(ARDUINO-AREF-Pad20)") (class "Default")
      (node (ref "ARDUINO") (pin "20") (pinfunction "AREF_20") (pintype "bidirectional"))
    )
    (net (code "104") (name "unconnected-(ARDUINO-MISO-Pad33)") (class "Default")
      (node (ref "ARDUINO") (pin "33") (pinfunction "MISO_33") (pintype "bidirectional"))
    )
    (net (code "105") (name "unconnected-(ARDUINO-NC_1-Pad27)") (class "Default")
      (node (ref "ARDUINO") (pin "27") (pinfunction "NC_1_27") (pintype "bidirectional"))
    )
    (net (code "106") (name "unconnected-(ARDUINO-NC_2-Pad28)") (class "Default")
      (node (ref "ARDUINO") (pin "28") (pinfunction "NC_2_28") (pintype "bidirectional"))
    )
    (net (code "107") (name "unconnected-(ARDUINO-RESET_1-Pad5)") (class "Default")
      (node (ref "ARDUINO") (pin "5") (pinfunction "RESET_1_5") (pintype "bidirectional"))
    )
    (net (code "108") (name "unconnected-(ARDUINO-RESET_2-Pad30)") (class "Default")
      (node (ref "ARDUINO") (pin "30") (pinfunction "RESET_2_30") (pintype "bidirectional"))
    )
    (net (code "109") (name "unconnected-(ARDUINO-SCK-Pad34)") (class "Default")
      (node (ref "ARDUINO") (pin "34") (pinfunction "SCK_34") (pintype "bidirectional"))
    )
    (net (code "110") (name "unconnected-(LCD-COM-PadP$1)") (class "Default")
      (node (ref "LCD") (pin "P$1") (pinfunction "COM_P$1") (pintype "bidirectional"))
    )
    (net (code "111") (name "unconnected-(LCD-COM-PadP$40)") (class "Default")
      (node (ref "LCD") (pin "P$40") (pinfunction "COM_P$40") (pintype "bidirectional"))
    )
    (net (code "112") (name "unconnected-(LCD-DP1-PadP$8)") (class "Default")
      (node (ref "LCD") (pin "P$8") (pinfunction "DP1_P$8") (pintype "bidirectional"))
    )
    (net (code "113") (name "unconnected-(LCD-LO_BAT-PadP$38)") (class "Default")
      (node (ref "LCD") (pin "P$38") (pinfunction "LO_BAT_P$38") (pintype "bidirectional"))
    )
    (net (code "114") (name "unconnected-(LCD-NC-PadP$4)") (class "Default")
      (node (ref "LCD") (pin "P$4") (pinfunction "NC_P$4") (pintype "bidirectional"))
    )
    (net (code "115") (name "unconnected-(LCD-NC-PadP$5)") (class "Default")
      (node (ref "LCD") (pin "P$5") (pinfunction "NC_P$5") (pintype "bidirectional"))
    )
    (net (code "116") (name "unconnected-(LCD-NC-PadP$6)") (class "Default")
      (node (ref "LCD") (pin "P$6") (pinfunction "NC_P$6") (pintype "bidirectional"))
    )
    (net (code "117") (name "unconnected-(LCD-NC-PadP$7)") (class "Default")
      (node (ref "LCD") (pin "P$7") (pinfunction "NC_P$7") (pintype "bidirectional"))
    )
    (net (code "118") (name "unconnected-(LCD-NC-PadP$33)") (class "Default")
      (node (ref "LCD") (pin "P$33") (pinfunction "NC_P$33") (pintype "bidirectional"))
    )
    (net (code "119") (name "unconnected-(LCD-NC-PadP$34)") (class "Default")
      (node (ref "LCD") (pin "P$34") (pinfunction "NC_P$34") (pintype "bidirectional"))
    )
    (net (code "120") (name "unconnected-(LCD-NC-PadP$35)") (class "Default")
      (node (ref "LCD") (pin "P$35") (pinfunction "NC_P$35") (pintype "bidirectional"))
    )
    (net (code "121") (name "unconnected-(LCD-NC-PadP$36)") (class "Default")
      (node (ref "LCD") (pin "P$36") (pinfunction "NC_P$36") (pintype "bidirectional"))
    )
    (net (code "122") (name "unconnected-(MUXGA-Y-Pad3)") (class "Default")
      (node (ref "MUXG") (pin "3") (pinfunction "Y_3") (pintype "bidirectional"))
    )
    (net (code "123") (name "unconnected-(MUXGA-Y0-Pad1)") (class "Default")
      (node (ref "MUXG") (pin "1") (pinfunction "Y0_1") (pintype "bidirectional"))
    )
    (net (code "124") (name "unconnected-(MUXGA-Y1-Pad5)") (class "Default")
      (node (ref "MUXG") (pin "5") (pinfunction "Y1_5") (pintype "bidirectional"))
    )
    (net (code "125") (name "unconnected-(MUXGA-Y2-Pad2)") (class "Default")
      (node (ref "MUXG") (pin "2") (pinfunction "Y2_2") (pintype "bidirectional"))
    )
    (net (code "126") (name "unconnected-(MUXGA-Y3-Pad4)") (class "Default")
      (node (ref "MUXG") (pin "4") (pinfunction "Y3_4") (pintype "bidirectional"))
    )
    (net (code "127") (name "unconnected-(THERMOCOUPLE-NC-Pad8)") (class "Default")
      (node (ref "THERMOCOUPLE") (pin "8") (pinfunction "NC_8") (pintype "bidirectional"))
    )
  )
)
